# CanNode.net
KiCad netlist of a schematic drawn in Altium Designer
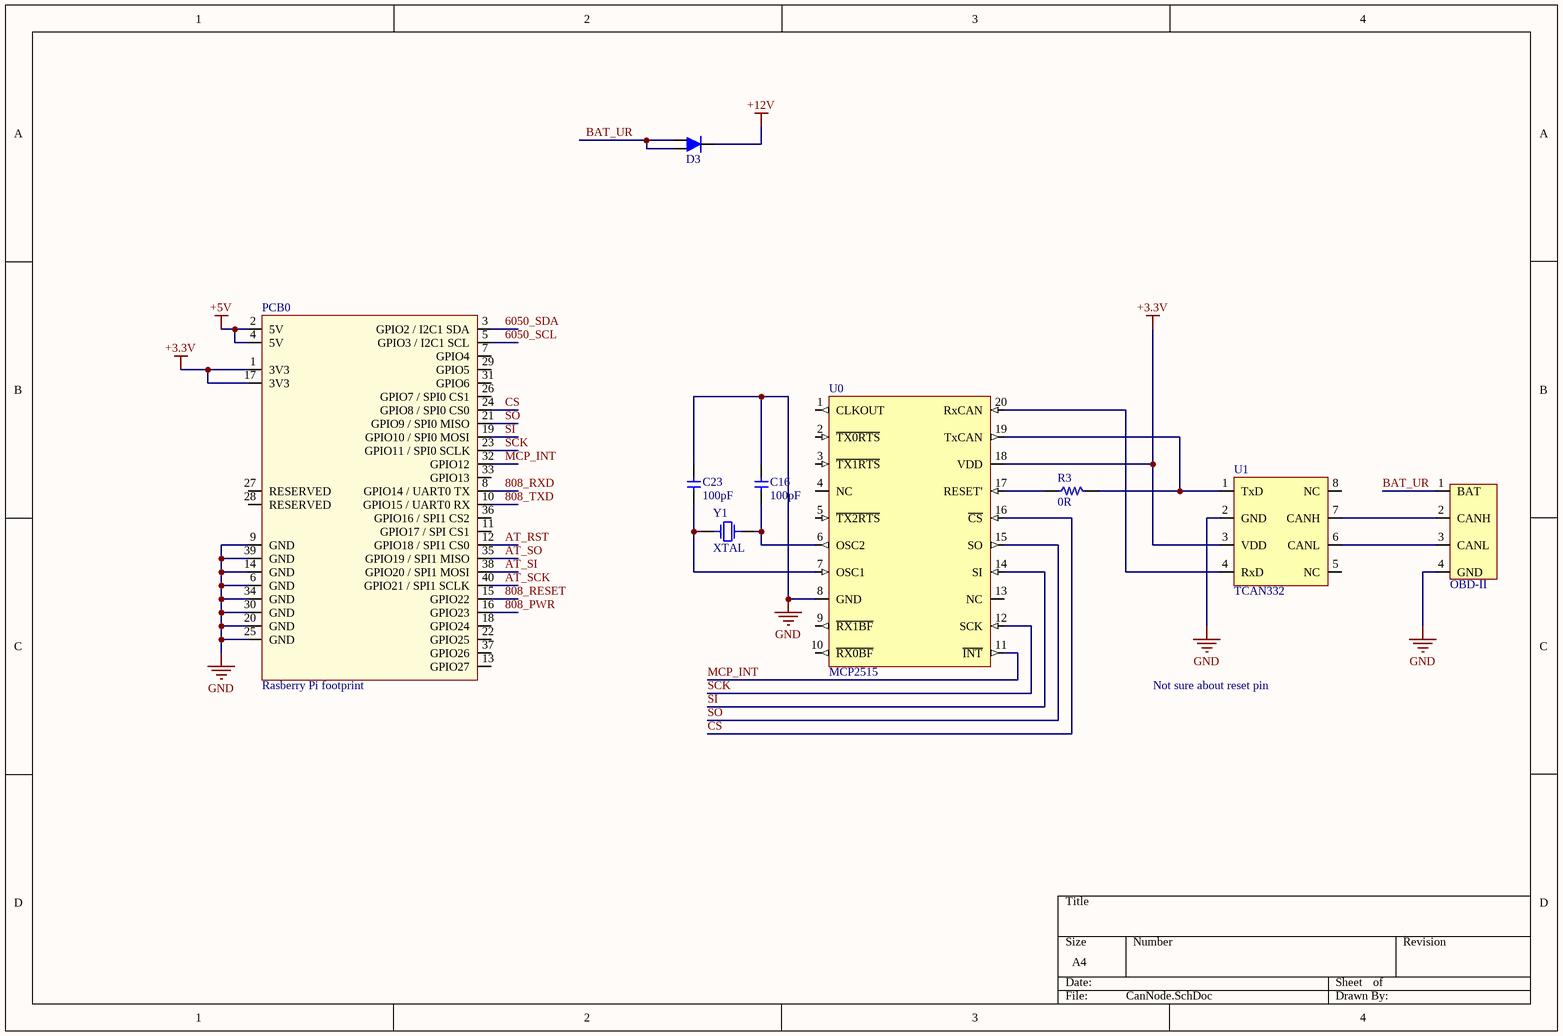
[diagram p0: CanNode.SchDoc]

(export (version "E")
  (design (tool "Eeschema 10.0.6"))
  (components
    (comp (ref "C16")
      (value "100pF")
      (footprint "0805")
      (description "Generic capacitor")
      (fields (field (name "Comment") "Generic Capacitor"))
      (libsource (lib "PowerCircuit") (part "Capacitor"))
    )
    (comp (ref "C23")
      (value "100pF")
      (footprint "0805")
      (description "Generic capacitor")
      (fields (field (name "Comment") "Generic Capacitor"))
      (libsource (lib "PowerCircuit") (part "Capacitor"))
    )
    (comp (ref "D3")
      (value "DIODE SCHOTTKY 60V 5A")
      (footprint "TO277A")
      (description "DIODE SCHOTTKY 60V 5A TO277A")
      (fields
        (field (name "MANUFACTURER") "Vishay Semiconductor Diodes Division")
        (field (name "MANUFACTURER PART NUMBER") "SS5P6-M3/86A")
      )
      (libsource (lib "PowerCircuit") (part "SS5P6-M3/86A"))
    )
    (comp (ref "OBD-II") (value "OBD-II") (footprint "OBD_II") (libsource (lib "CanNode") (part "OBD-II")))
    (comp (ref "PCB0")
      (value "Rasberry Pi footprint")
      (footprint "Rasberry PI")
      (libsource (lib "CanNode") (part "Rasberry Pi"))
    )
    (comp (ref "R3")
      (value "0R")
      (footprint "0805")
      (description "Generic Resistor")
      (fields (field (name "Comment") "Resistor"))
      (libsource (lib "PowerCircuit") (part "Resistor"))
    )
    (comp (ref "U0")
      (value "MCP2515")
      (footprint "MCP2515")
      (description "IC CAN CTLR W/SPI 2.0B 20-QFN")
      (fields
        (field (name "DIGI-KEY PART NUMBER") "MCP2515T-I/MLCT-ND")
        (field (name "NOTES") "Not sure about reset pin")
      )
      (libsource (lib "CanNode") (part "MCP2515"))
    )
    (comp (ref "U1")
      (value "TCAN332")
      (footprint "SOIC-8")
      (description "IC TXRX CAN 8SOIC")
      (fields (field (name "DIGI-KEY PART NUMBER") "296-43711-1-ND"))
      (libsource (lib "CanNode") (part "TCAN332"))
    )
    (comp (ref "Y1")
      (value "XTAL")
      (footprint "XTAL-16.000")
      (description "XTAL16.0000MHZ 18PF SMD")
      (fields
        (field (name "MANUFACTURER") "Abracon LLC")
        (field (name "MANUFACTURER PART NUMBER") "ABM7-16.000MHZ-D2Y-T")
      )
      (libsource (lib "CanNode") (part "XTAL-16.000"))
    )
  )
  (nets
    (net (code "1") (name "+3.3V") (class "Default")
      (node (ref "PCB0") (pin "1") (pinfunction "3V3_1") (pintype "passive"))
      (node (ref "PCB0") (pin "17") (pinfunction "3V3_17") (pintype "passive"))
      (node (ref "U0") (pin "18") (pinfunction "VDD_18") (pintype "power_in"))
      (node (ref "U1") (pin "3") (pinfunction "VDD_3") (pintype "passive"))
    )
    (net (code "2") (name "+5V") (class "Default")
      (node (ref "PCB0") (pin "2") (pinfunction "5V_2") (pintype "passive"))
      (node (ref "PCB0") (pin "4") (pinfunction "5V_4") (pintype "passive"))
    )
    (net (code "3") (name "+12V") (class "Default")
      (node (ref "D3") (pin "3") (pinfunction "3_3") (pintype "passive"))
    )
    (net (code "4") (name "/808_PWR") (class "Default")
      (node (ref "PCB0") (pin "16") (pinfunction "GPIO23_16") (pintype "passive"))
    )
    (net (code "5") (name "/808_RESET") (class "Default")
      (node (ref "PCB0") (pin "15") (pinfunction "GPIO22_15") (pintype "passive"))
    )
    (net (code "6") (name "/808_RXD") (class "Default")
      (node (ref "PCB0") (pin "8") (pinfunction "GPIO14_/_UART0_TX_8") (pintype "passive"))
    )
    (net (code "7") (name "/808_TXD") (class "Default")
      (node (ref "PCB0") (pin "10") (pinfunction "GPIO15_/_UART0_RX_10") (pintype "passive"))
    )
    (net (code "8") (name "/6050_SCL") (class "Default")
      (node (ref "PCB0") (pin "5") (pinfunction "GPIO3_/_I2C1_SCL_5") (pintype "passive"))
    )
    (net (code "9") (name "/6050_SDA") (class "Default")
      (node (ref "PCB0") (pin "3") (pinfunction "GPIO2_/_I2C1_SDA_3") (pintype "passive"))
    )
    (net (code "10") (name "/AT_RST") (class "Default")
      (node (ref "PCB0") (pin "12") (pinfunction "GPIO18_/_SPI1_CS0_12") (pintype "passive"))
    )
    (net (code "11") (name "/AT_SCK") (class "Default")
      (node (ref "PCB0") (pin "40") (pinfunction "GPIO21_/_SPI1_SCLK_40") (pintype "passive"))
    )
    (net (code "12") (name "/AT_SI") (class "Default")
      (node (ref "PCB0") (pin "38") (pinfunction "GPIO20_/_SPI1_MOSI_38") (pintype "passive"))
    )
    (net (code "13") (name "/AT_SO") (class "Default")
      (node (ref "PCB0") (pin "35") (pinfunction "GPIO19_/_SPI1_MISO_35") (pintype "passive"))
    )
    (net (code "14") (name "/BAT_UR") (class "Default")
      (node (ref "D3") (pin "1") (pinfunction "1_1") (pintype "passive"))
      (node (ref "D3") (pin "2") (pinfunction "2_2") (pintype "passive"))
      (node (ref "OBD-II") (pin "1") (pinfunction "BAT_1") (pintype "passive"))
    )
    (net (code "15") (name "/CS") (class "Default")
      (node (ref "PCB0") (pin "24") (pinfunction "GPIO8_/_SPI0_CS0_24") (pintype "passive"))
      (node (ref "U0") (pin "16") (pinfunction "~{CS}_16") (pintype "input"))
    )
    (net (code "16") (name "/MCP_INT") (class "Default")
      (node (ref "PCB0") (pin "32") (pinfunction "GPIO12_32") (pintype "passive"))
      (node (ref "U0") (pin "11") (pinfunction "~{INT}_11") (pintype "output"))
    )
    (net (code "17") (name "/SCK") (class "Default")
      (node (ref "PCB0") (pin "23") (pinfunction "GPIO11_/_SPI0_SCLK_23") (pintype "passive"))
      (node (ref "U0") (pin "12") (pinfunction "SCK_12") (pintype "input"))
    )
    (net (code "18") (name "/SI") (class "Default")
      (node (ref "PCB0") (pin "19") (pinfunction "GPIO10_/_SPI0_MOSI_19") (pintype "passive"))
      (node (ref "U0") (pin "14") (pinfunction "SI_14") (pintype "input"))
    )
    (net (code "19") (name "/SO") (class "Default")
      (node (ref "PCB0") (pin "21") (pinfunction "GPIO9_/_SPI0_MISO_21") (pintype "passive"))
      (node (ref "U0") (pin "15") (pinfunction "SO_15") (pintype "output"))
    )
    (net (code "20") (name "GND") (class "Default")
      (node (ref "C16") (pin "2") (pinfunction "2_2") (pintype "passive"))
      (node (ref "C23") (pin "2") (pinfunction "2_2") (pintype "passive"))
      (node (ref "OBD-II") (pin "4") (pinfunction "GND_4") (pintype "passive"))
      (node (ref "PCB0") (pin "14") (pinfunction "GND_14") (pintype "passive"))
      (node (ref "PCB0") (pin "20") (pinfunction "GND_20") (pintype "passive"))
      (node (ref "PCB0") (pin "25") (pinfunction "GND_25") (pintype "passive"))
      (node (ref "PCB0") (pin "30") (pinfunction "GND_30") (pintype "passive"))
      (node (ref "PCB0") (pin "34") (pinfunction "GND_34") (pintype "passive"))
      (node (ref "PCB0") (pin "39") (pinfunction "GND_39") (pintype "passive"))
      (node (ref "PCB0") (pin "6") (pinfunction "GND_6") (pintype "passive"))
      (node (ref "PCB0") (pin "9") (pinfunction "GND_9") (pintype "passive"))
      (node (ref "U0") (pin "8") (pinfunction "GND_8") (pintype "power_in"))
      (node (ref "U1") (pin "2") (pinfunction "GND_2") (pintype "passive"))
    )
    (net (code "21") (name "Net-(OBD-II-CANH)") (class "Default")
      (node (ref "OBD-II") (pin "2") (pinfunction "CANH_2") (pintype "passive"))
      (node (ref "U1") (pin "7") (pinfunction "CANH_7") (pintype "passive"))
    )
    (net (code "22") (name "Net-(OBD-II-CANL)") (class "Default")
      (node (ref "OBD-II") (pin "3") (pinfunction "CANL_3") (pintype "passive"))
      (node (ref "U1") (pin "6") (pinfunction "CANL_6") (pintype "passive"))
    )
    (net (code "23") (name "Net-(U0-OSC1)") (class "Default")
      (node (ref "C23") (pin "1") (pinfunction "1_1") (pintype "passive"))
      (node (ref "U0") (pin "7") (pinfunction "OSC1_7") (pintype "input"))
      (node (ref "Y1") (pin "0") (pinfunction "0_0") (pintype "passive"))
    )
    (net (code "24") (name "Net-(U0-OSC2)") (class "Default")
      (node (ref "C16") (pin "1") (pinfunction "1_1") (pintype "passive"))
      (node (ref "U0") (pin "6") (pinfunction "OSC2_6") (pintype "output"))
      (node (ref "Y1") (pin "1") (pinfunction "1_1") (pintype "passive"))
    )
    (net (code "25") (name "Net-(U0-RESET')") (class "Default")
      (node (ref "R3") (pin "1") (pinfunction "1_1") (pintype "passive"))
      (node (ref "U0") (pin "17") (pinfunction "RESET'_17") (pintype "input"))
    )
    (net (code "26") (name "Net-(U0-RxCAN)") (class "Default")
      (node (ref "U0") (pin "20") (pinfunction "RxCAN_20") (pintype "input"))
      (node (ref "U1") (pin "4") (pinfunction "RxD_4") (pintype "passive"))
    )
    (net (code "27") (name "Net-(U0-TxCAN)") (class "Default")
      (node (ref "R3") (pin "2") (pinfunction "2_2") (pintype "passive"))
      (node (ref "U0") (pin "19") (pinfunction "TxCAN_19") (pintype "output"))
      (node (ref "U1") (pin "1") (pinfunction "TxD_1") (pintype "passive"))
    )
    (net (code "28") (name "unconnected-(PCB0-GPIO4-Pad7)") (class "Default")
      (node (ref "PCB0") (pin "7") (pinfunction "GPIO4_7") (pintype "passive"))
    )
    (net (code "29") (name "unconnected-(PCB0-GPIO5-Pad29)") (class "Default")
      (node (ref "PCB0") (pin "29") (pinfunction "GPIO5_29") (pintype "passive"))
    )
    (net (code "30") (name "unconnected-(PCB0-GPIO6-Pad31)") (class "Default")
      (node (ref "PCB0") (pin "31") (pinfunction "GPIO6_31") (pintype "passive"))
    )
    (net (code "31") (name "unconnected-(PCB0-GPIO7_{slash}_SPI0_CS1-Pad26)") (class "Default")
      (node (ref "PCB0") (pin "26") (pinfunction "GPIO7_/_SPI0_CS1_26") (pintype "passive"))
    )
    (net (code "32") (name "unconnected-(PCB0-GPIO13-Pad33)") (class "Default")
      (node (ref "PCB0") (pin "33") (pinfunction "GPIO13_33") (pintype "passive"))
    )
    (net (code "33") (name "unconnected-(PCB0-GPIO16_{slash}_SPI1_CS2-Pad36)") (class "Default")
      (node (ref "PCB0") (pin "36") (pinfunction "GPIO16_/_SPI1_CS2_36") (pintype "passive"))
    )
    (net (code "34") (name "unconnected-(PCB0-GPIO17_{slash}_SPI_CS1-Pad11)") (class "Default")
      (node (ref "PCB0") (pin "11") (pinfunction "GPIO17_/_SPI_CS1_11") (pintype "passive"))
    )
    (net (code "35") (name "unconnected-(PCB0-GPIO24-Pad18)") (class "Default")
      (node (ref "PCB0") (pin "18") (pinfunction "GPIO24_18") (pintype "passive"))
    )
    (net (code "36") (name "unconnected-(PCB0-GPIO25-Pad22)") (class "Default")
      (node (ref "PCB0") (pin "22") (pinfunction "GPIO25_22") (pintype "passive"))
    )
    (net (code "37") (name "unconnected-(PCB0-GPIO26-Pad37)") (class "Default")
      (node (ref "PCB0") (pin "37") (pinfunction "GPIO26_37") (pintype "passive"))
    )
    (net (code "38") (name "unconnected-(PCB0-GPIO27-Pad13)") (class "Default")
      (node (ref "PCB0") (pin "13") (pinfunction "GPIO27_13") (pintype "passive"))
    )
    (net (code "39") (name "unconnected-(PCB0-RESERVED-Pad27)") (class "Default")
      (node (ref "PCB0") (pin "27") (pinfunction "RESERVED_27") (pintype "passive"))
    )
    (net (code "40") (name "unconnected-(PCB0-RESERVED-Pad28)") (class "Default")
      (node (ref "PCB0") (pin "28") (pinfunction "RESERVED_28") (pintype "passive"))
    )
    (net (code "41") (name "unconnected-(U0-CLKOUT-Pad1)") (class "Default")
      (node (ref "U0") (pin "1") (pinfunction "CLKOUT_1") (pintype "output"))
    )
    (net (code "42") (name "unconnected-(U0-NC-Pad4)") (class "Default")
      (node (ref "U0") (pin "4") (pinfunction "NC_4") (pintype "passive"))
    )
    (net (code "43") (name "unconnected-(U0-NC-Pad13)") (class "Default")
      (node (ref "U0") (pin "13") (pinfunction "NC_13") (pintype "passive"))
    )
    (net (code "44") (name "unconnected-(U0-~{RX0BF}-Pad10)") (class "Default")
      (node (ref "U0") (pin "10") (pinfunction "~{RX0BF}_10") (pintype "output"))
    )
    (net (code "45") (name "unconnected-(U0-~{RX1BF}-Pad9)") (class "Default")
      (node (ref "U0") (pin "9") (pinfunction "~{RX1BF}_9") (pintype "output"))
    )
    (net (code "46") (name "unconnected-(U0-~{TX0RTS}-Pad2)") (class "Default")
      (node (ref "U0") (pin "2") (pinfunction "~{TX0RTS}_2") (pintype "input"))
    )
    (net (code "47") (name "unconnected-(U0-~{TX1RTS}-Pad3)") (class "Default")
      (node (ref "U0") (pin "3") (pinfunction "~{TX1RTS}_3") (pintype "input"))
    )
    (net (code "48") (name "unconnected-(U0-~{TX2RTS}-Pad5)") (class "Default")
      (node (ref "U0") (pin "5") (pinfunction "~{TX2RTS}_5") (pintype "input"))
    )
    (net (code "49") (name "unconnected-(U1-NC-Pad5)") (class "Default")
      (node (ref "U1") (pin "5") (pinfunction "NC_5") (pintype "passive"))
    )
    (net (code "50") (name "unconnected-(U1-NC-Pad8)") (class "Default")
      (node (ref "U1") (pin "8") (pinfunction "NC_8") (pintype "passive"))
    )
  )
)
